# micromouse.net
KiCad netlist of a schematic drawn in EAGLE
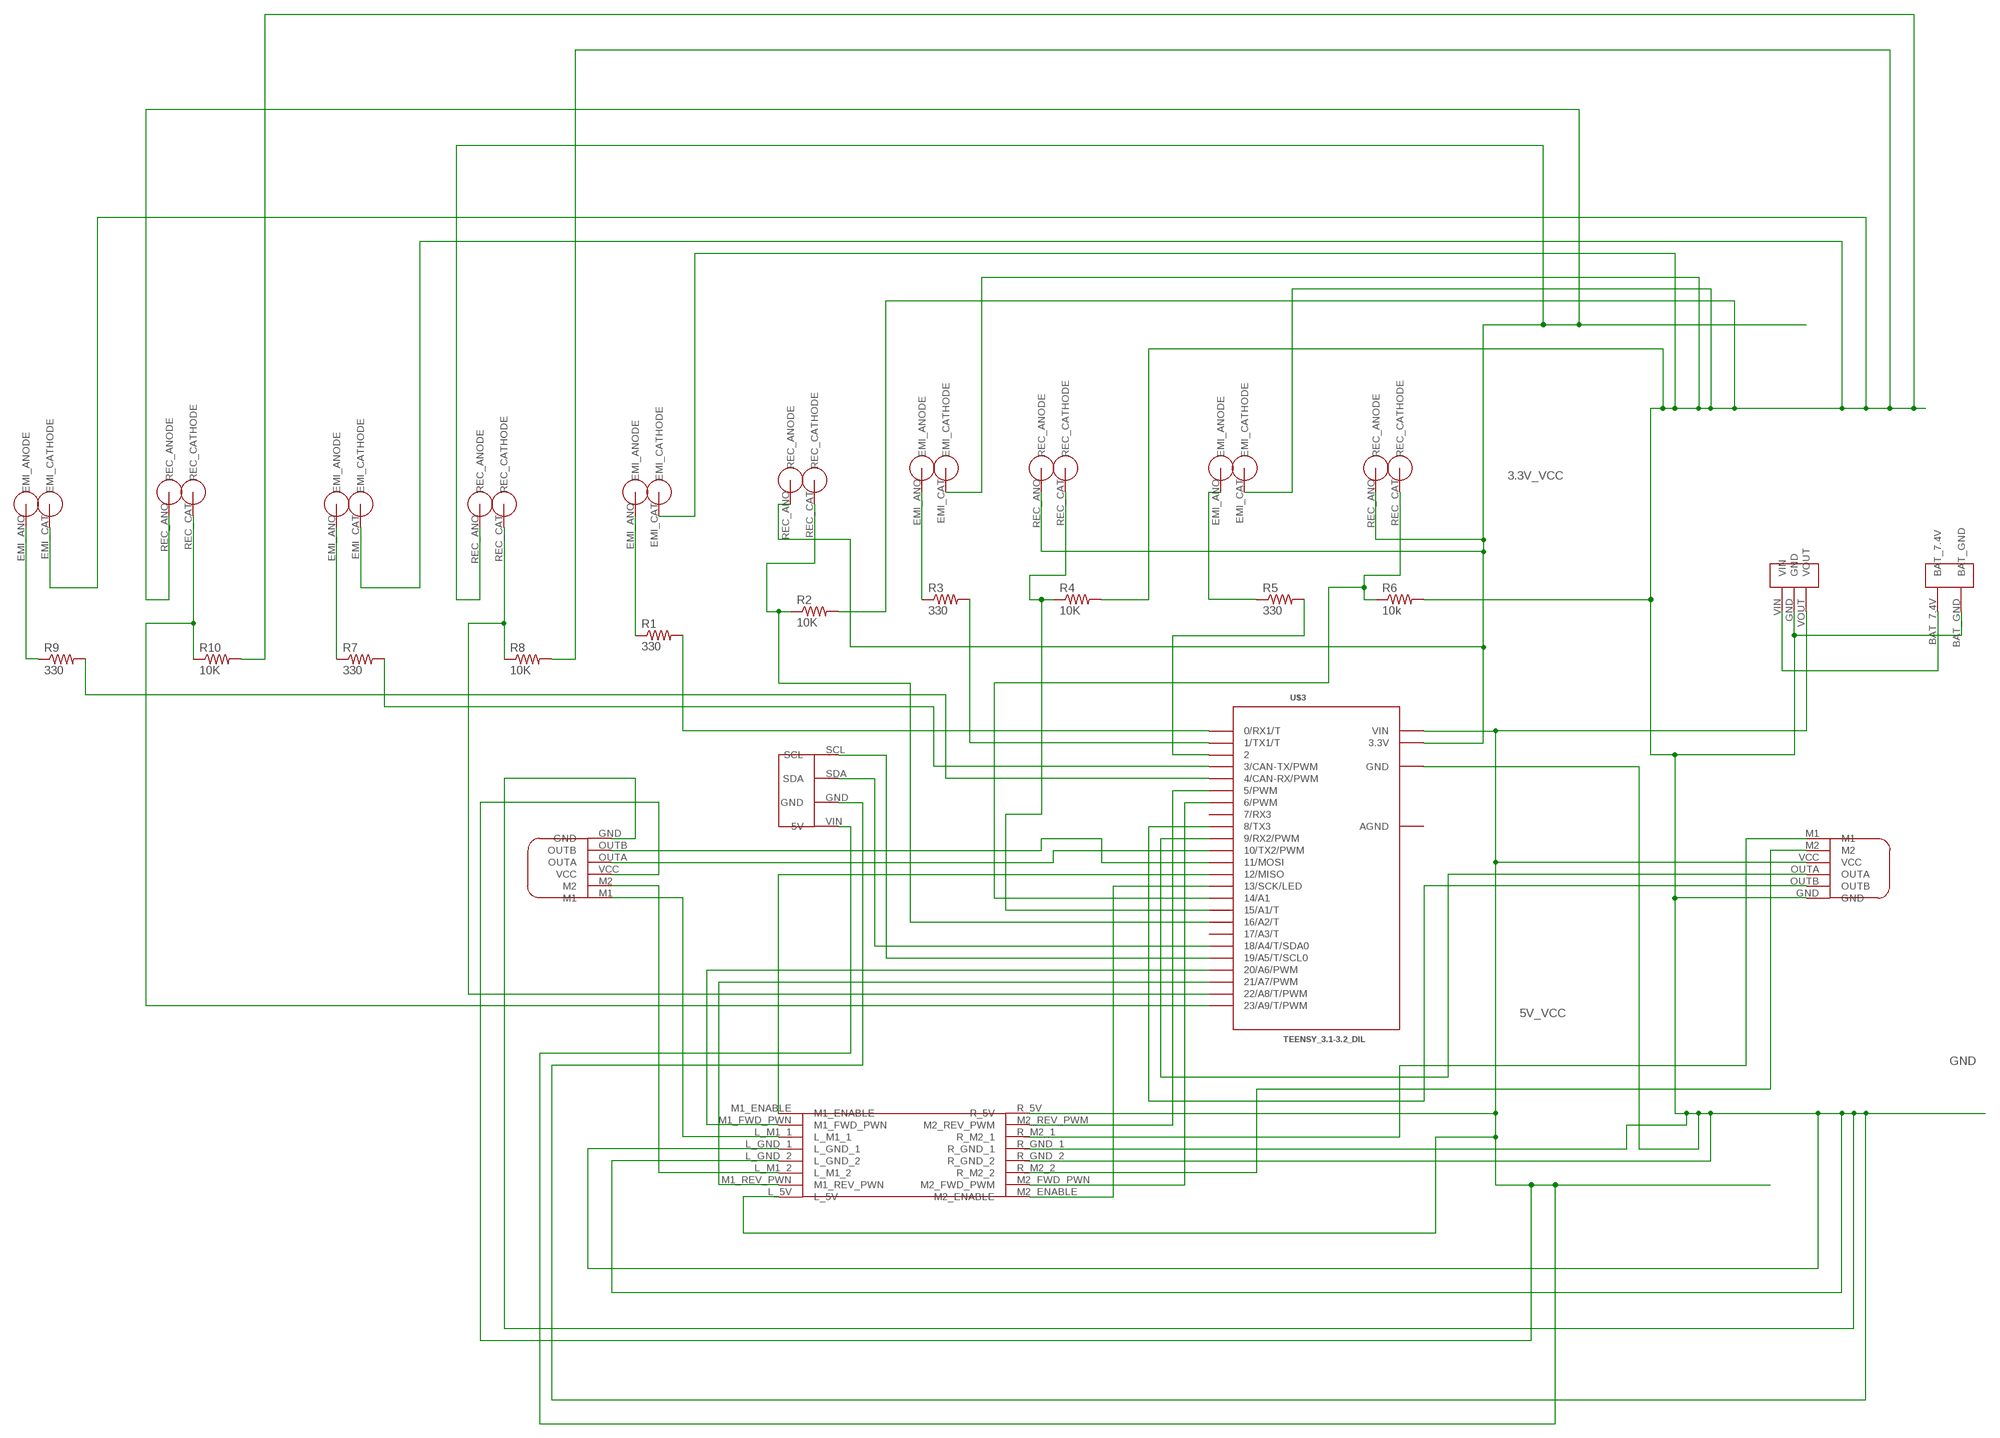
[diagram p0: schematic, sheet 1]

(export (version "E")
  (design (tool "Eeschema 10.0.6"))
  (components
    (comp (ref "R1")
      (value "330")
      (footprint "eagle-import:0207_10")
      (libsource (lib "eagle-import") (part "R-US_0207/10"))
    )
    (comp (ref "R2")
      (value "10K")
      (footprint "eagle-import:0207_10")
      (libsource (lib "eagle-import") (part "R-US_0207/10"))
    )
    (comp (ref "R3")
      (value "330")
      (footprint "eagle-import:0207_10")
      (libsource (lib "eagle-import") (part "R-US_0207/10"))
    )
    (comp (ref "R4")
      (value "10K")
      (footprint "eagle-import:0207_10")
      (libsource (lib "eagle-import") (part "R-US_0207/10"))
    )
    (comp (ref "R5")
      (value "330")
      (footprint "eagle-import:0207_10")
      (libsource (lib "eagle-import") (part "R-US_0207/10"))
    )
    (comp (ref "R6")
      (value "10k")
      (footprint "eagle-import:0207_10")
      (libsource (lib "eagle-import") (part "R-US_0207/10"))
    )
    (comp (ref "R7")
      (value "330")
      (footprint "eagle-import:0207_10")
      (libsource (lib "eagle-import") (part "R-US_0207/10"))
    )
    (comp (ref "R8")
      (value "10K")
      (footprint "eagle-import:0207_10")
      (libsource (lib "eagle-import") (part "R-US_0207/10"))
    )
    (comp (ref "R9")
      (value "330")
      (footprint "eagle-import:0207_10")
      (libsource (lib "eagle-import") (part "R-US_0207/10"))
    )
    (comp (ref "R10")
      (value "10K")
      (footprint "eagle-import:0207_10")
      (libsource (lib "eagle-import") (part "R-US_0207/10"))
    )
    (comp (ref "U$1")
      (value "MOTOR_ENCODER")
      (footprint "eagle-import:MOTOR_ENCODER")
      (libsource (lib "eagle-import") (part "MOTOR_ENCODER"))
    )
    (comp (ref "U$2")
      (value "MOTOR_ENCODER")
      (footprint "eagle-import:MOTOR_ENCODER")
      (libsource (lib "eagle-import") (part "MOTOR_ENCODER"))
    )
    (comp (ref "U$3")
      (value "TEENSY_3.1-3.2_DIL")
      (footprint "eagle-import:TEENSY_3.0-3.2&LC_DIL")
      (libsource (lib "eagle-import") (part "TEENSY_3.1-3.2_DIL"))
    )
    (comp (ref "U$4")
      (value "MOTOR_DRIVER")
      (footprint "eagle-import:MOTOR_DRIVER")
      (libsource (lib "eagle-import") (part "MOTOR_DRIVER"))
    )
    (comp (ref "U$5")
      (value "IR_RECIEVER")
      (footprint "eagle-import:IR_RECIEVER")
      (libsource (lib "eagle-import") (part "IR_RECIEVER"))
    )
    (comp (ref "U$6")
      (value "IR_EMITTER")
      (footprint "eagle-import:IR_EMITTER")
      (libsource (lib "eagle-import") (part "IR_EMITTER"))
    )
    (comp (ref "U$7")
      (value "IR_EMITTER")
      (footprint "eagle-import:IR_EMITTER")
      (libsource (lib "eagle-import") (part "IR_EMITTER"))
    )
    (comp (ref "U$8")
      (value "IR_RECIEVER")
      (footprint "eagle-import:IR_RECIEVER")
      (libsource (lib "eagle-import") (part "IR_RECIEVER"))
    )
    (comp (ref "U$9")
      (value "IR_EMITTER")
      (footprint "eagle-import:IR_EMITTER")
      (libsource (lib "eagle-import") (part "IR_EMITTER"))
    )
    (comp (ref "U$10")
      (value "VOLTAGE_REGULATOR")
      (footprint "eagle-import:VOLTAGE_REGULATOR")
      (libsource (lib "eagle-import") (part "VOLTAGE_REGULATOR"))
    )
    (comp (ref "U$11")
      (value "BATTERY_INPUT")
      (footprint "eagle-import:BATTERY_INPUT")
      (libsource (lib "eagle-import") (part "BATTERY_INPUT"))
    )
    (comp (ref "U$12")
      (value "IR_RECIEVER")
      (footprint "eagle-import:IR_RECIEVER")
      (libsource (lib "eagle-import") (part "IR_RECIEVER"))
    )
    (comp (ref "U$13")
      (value "IMU")
      (footprint "eagle-import:IMU")
      (libsource (lib "eagle-import") (part "IMU"))
    )
    (comp (ref "U$14")
      (value "IR_EMITTER")
      (footprint "eagle-import:IR_EMITTER")
      (libsource (lib "eagle-import") (part "IR_EMITTER"))
    )
    (comp (ref "U$15")
      (value "IR_RECIEVER")
      (footprint "eagle-import:IR_RECIEVER")
      (libsource (lib "eagle-import") (part "IR_RECIEVER"))
    )
    (comp (ref "U$16")
      (value "IR_EMITTER")
      (footprint "eagle-import:IR_EMITTER")
      (libsource (lib "eagle-import") (part "IR_EMITTER"))
    )
    (comp (ref "U$17")
      (value "IR_RECIEVER")
      (footprint "eagle-import:IR_RECIEVER")
      (libsource (lib "eagle-import") (part "IR_RECIEVER"))
    )
  )
  (nets
    (net (code "1") (name "/3.3V_VCC") (class "Default")
      (node (ref "U$12") (pin "REC_ANO") (pinfunction "REC_ANODE_REC_ANO") (pintype "bidirectional"))
      (node (ref "U$15") (pin "REC_ANO") (pinfunction "REC_ANODE_REC_ANO") (pintype "bidirectional"))
      (node (ref "U$17") (pin "REC_ANO") (pinfunction "REC_ANODE_REC_ANO") (pintype "bidirectional"))
      (node (ref "U$3") (pin "3.3V") (pinfunction "3.3V_3.3V") (pintype "power_in"))
      (node (ref "U$5") (pin "REC_ANO") (pinfunction "REC_ANODE_REC_ANO") (pintype "bidirectional"))
      (node (ref "U$8") (pin "REC_ANO") (pinfunction "REC_ANODE_REC_ANO") (pintype "bidirectional"))
    )
    (net (code "2") (name "/5V_VCC") (class "Default")
      (node (ref "U$1") (pin "VCC") (pinfunction "VCC_VCC") (pintype "bidirectional"))
      (node (ref "U$10") (pin "VOUT") (pinfunction "VOUT_VOUT") (pintype "bidirectional"))
      (node (ref "U$13") (pin "VIN") (pinfunction "5V_VIN") (pintype "bidirectional"))
      (node (ref "U$2") (pin "VCC") (pinfunction "VCC_VCC") (pintype "bidirectional"))
      (node (ref "U$3") (pin "VIN") (pinfunction "VIN_VIN") (pintype "power_in"))
      (node (ref "U$4") (pin "L_5V") (pinfunction "L_5V_L_5V") (pintype "bidirectional"))
      (node (ref "U$4") (pin "R_5V") (pinfunction "R_5V_R_5V") (pintype "bidirectional"))
    )
    (net (code "3") (name "/AGND") (class "Default")
      (node (ref "U$3") (pin "AGND") (pinfunction "AGND_AGND") (pintype "power_in"))
    )
    (net (code "4") (name "/GND") (class "Default")
      (node (ref "R10") (pin "2") (pinfunction "2_2") (pintype "passive"))
      (node (ref "R2") (pin "2") (pinfunction "2_2") (pintype "passive"))
      (node (ref "R4") (pin "2") (pinfunction "2_2") (pintype "passive"))
      (node (ref "R6") (pin "2") (pinfunction "2_2") (pintype "passive"))
      (node (ref "R8") (pin "2") (pinfunction "2_2") (pintype "passive"))
      (node (ref "U$1") (pin "GND") (pinfunction "GND_GND") (pintype "bidirectional"))
      (node (ref "U$10") (pin "GND") (pinfunction "GND_GND") (pintype "bidirectional"))
      (node (ref "U$11") (pin "BAT_GND") (pinfunction "BAT_GND_BAT_GND") (pintype "bidirectional"))
      (node (ref "U$13") (pin "GND") (pinfunction "GND_GND") (pintype "bidirectional"))
      (node (ref "U$14") (pin "EMI_CAT") (pinfunction "EMI_CATHODE_EMI_CAT") (pintype "bidirectional"))
      (node (ref "U$16") (pin "EMI_CAT") (pinfunction "EMI_CATHODE_EMI_CAT") (pintype "bidirectional"))
      (node (ref "U$2") (pin "GND") (pinfunction "GND_GND") (pintype "bidirectional"))
      (node (ref "U$3") (pin "GND") (pinfunction "GND_GND") (pintype "power_in"))
      (node (ref "U$4") (pin "L_GND_1") (pinfunction "L_GND_1_L_GND_1") (pintype "bidirectional"))
      (node (ref "U$4") (pin "L_GND_2") (pinfunction "L_GND_2_L_GND_2") (pintype "bidirectional"))
      (node (ref "U$4") (pin "R_GND_1") (pinfunction "R_GND_1_R_GND_1") (pintype "bidirectional"))
      (node (ref "U$4") (pin "R_GND_2") (pinfunction "R_GND_2_R_GND_2") (pintype "bidirectional"))
      (node (ref "U$6") (pin "EMI_CAT") (pinfunction "EMI_CATHODE_EMI_CAT") (pintype "bidirectional"))
      (node (ref "U$7") (pin "EMI_CAT") (pinfunction "EMI_CATHODE_EMI_CAT") (pintype "bidirectional"))
      (node (ref "U$9") (pin "EMI_CAT") (pinfunction "EMI_CATHODE_EMI_CAT") (pintype "bidirectional"))
    )
    (net (code "5") (name "Net-(R5-Pad2)") (class "Default")
      (node (ref "R5") (pin "2") (pinfunction "2_2") (pintype "passive"))
      (node (ref "U$3") (pin "2") (pinfunction "2_2") (pintype "bidirectional"))
    )
    (net (code "6") (name "Net-(U$1-PadM1)") (class "Default")
      (node (ref "U$1") (pin "M1") (pinfunction "M1_M1") (pintype "bidirectional"))
      (node (ref "U$4") (pin "L_M1_1") (pinfunction "L_M1_1_L_M1_1") (pintype "bidirectional"))
    )
    (net (code "7") (name "Net-(U$1-PadM2)") (class "Default")
      (node (ref "U$1") (pin "M2") (pinfunction "M2_M2") (pintype "bidirectional"))
      (node (ref "U$4") (pin "L_M1_2") (pinfunction "L_M1_2_L_M1_2") (pintype "bidirectional"))
    )
    (net (code "8") (name "Net-(U$2-PadM1)") (class "Default")
      (node (ref "U$2") (pin "M1") (pinfunction "M1_M1") (pintype "bidirectional"))
      (node (ref "U$4") (pin "R_M2_1") (pinfunction "R_M2_1_R_M2_1") (pintype "bidirectional"))
    )
    (net (code "9") (name "Net-(U$2-PadM2)") (class "Default")
      (node (ref "U$2") (pin "M2") (pinfunction "M2_M2") (pintype "bidirectional"))
      (node (ref "U$4") (pin "R_M2_2") (pinfunction "R_M2_2_R_M2_2") (pintype "bidirectional"))
    )
    (net (code "10") (name "Net-(U$3-0{slash}RX1{slash}T)") (class "Default")
      (node (ref "R1") (pin "2") (pinfunction "2_2") (pintype "passive"))
      (node (ref "U$3") (pin "0") (pinfunction "0/RX1/T_0") (pintype "bidirectional"))
    )
    (net (code "11") (name "Net-(U$3-1{slash}TX1{slash}T)") (class "Default")
      (node (ref "R3") (pin "2") (pinfunction "2_2") (pintype "passive"))
      (node (ref "U$3") (pin "1") (pinfunction "1/TX1/T_1") (pintype "bidirectional"))
    )
    (net (code "12") (name "Net-(U$3-3{slash}CAN-TX{slash}PWM)") (class "Default")
      (node (ref "R7") (pin "2") (pinfunction "2_2") (pintype "passive"))
      (node (ref "U$3") (pin "3") (pinfunction "3/CAN-TX/PWM_3") (pintype "bidirectional"))
    )
    (net (code "13") (name "Net-(U$3-4{slash}CAN-RX{slash}PWM)") (class "Default")
      (node (ref "R9") (pin "2") (pinfunction "2_2") (pintype "passive"))
      (node (ref "U$3") (pin "4") (pinfunction "4/CAN-RX/PWM_4") (pintype "bidirectional"))
    )
    (net (code "14") (name "Net-(U$3-5{slash}PWM)") (class "Default")
      (node (ref "U$3") (pin "5") (pinfunction "5/PWM_5") (pintype "bidirectional"))
      (node (ref "U$4") (pin "M2_REV_PWM") (pinfunction "M2_REV_PWM_M2_REV_PWM") (pintype "bidirectional"))
    )
    (net (code "15") (name "Net-(U$3-6{slash}PWM)") (class "Default")
      (node (ref "U$3") (pin "6") (pinfunction "6/PWM_6") (pintype "bidirectional"))
      (node (ref "U$4") (pin "M2_FWD_PWN") (pinfunction "M2_FWD_PWM_M2_FWD_PWN") (pintype "bidirectional"))
    )
    (net (code "16") (name "Net-(U$3-8{slash}TX3)") (class "Default")
      (node (ref "U$2") (pin "OUTB") (pinfunction "OUTB_OUTB") (pintype "bidirectional"))
      (node (ref "U$3") (pin "8") (pinfunction "8/TX3_8") (pintype "bidirectional"))
    )
    (net (code "17") (name "Net-(U$3-9{slash}RX2{slash}PWM)") (class "Default")
      (node (ref "U$2") (pin "OUTA") (pinfunction "OUTA_OUTA") (pintype "bidirectional"))
      (node (ref "U$3") (pin "9") (pinfunction "9/RX2/PWM_9") (pintype "bidirectional"))
    )
    (net (code "18") (name "Net-(U$3-10{slash}TX2{slash}PWM)") (class "Default")
      (node (ref "U$1") (pin "OUTA") (pinfunction "OUTA_OUTA") (pintype "bidirectional"))
      (node (ref "U$3") (pin "10") (pinfunction "10/TX2/PWM_10") (pintype "bidirectional"))
    )
    (net (code "19") (name "Net-(U$3-11{slash}MOSI)") (class "Default")
      (node (ref "U$1") (pin "OUTB") (pinfunction "OUTB_OUTB") (pintype "bidirectional"))
      (node (ref "U$3") (pin "11") (pinfunction "11/MOSI_11") (pintype "bidirectional"))
    )
    (net (code "20") (name "Net-(U$3-12{slash}MISO)") (class "Default")
      (node (ref "U$3") (pin "12") (pinfunction "12/MISO_12") (pintype "bidirectional"))
      (node (ref "U$4") (pin "M1_ENABLE") (pinfunction "M1_ENABLE_M1_ENABLE") (pintype "bidirectional"))
    )
    (net (code "21") (name "Net-(U$3-13{slash}SCK{slash}LED)") (class "Default")
      (node (ref "U$3") (pin "13") (pinfunction "13/SCK/LED_13") (pintype "bidirectional"))
      (node (ref "U$4") (pin "M2_ENABLE") (pinfunction "M2_ENABLE_M2_ENABLE") (pintype "bidirectional"))
    )
    (net (code "22") (name "Net-(U$3-14{slash}A1)") (class "Default")
      (node (ref "R6") (pin "1") (pinfunction "1_1") (pintype "passive"))
      (node (ref "U$3") (pin "14/A0") (pinfunction "14/A1_14/A0") (pintype "bidirectional"))
      (node (ref "U$8") (pin "REC_CAT") (pinfunction "REC_CATHODE_REC_CAT") (pintype "bidirectional"))
    )
    (net (code "23") (name "Net-(U$3-16{slash}A2{slash}T)") (class "Default")
      (node (ref "R2") (pin "1") (pinfunction "1_1") (pintype "passive"))
      (node (ref "U$3") (pin "16/A2") (pinfunction "16/A2/T_16/A2") (pintype "bidirectional"))
      (node (ref "U$5") (pin "REC_CAT") (pinfunction "REC_CATHODE_REC_CAT") (pintype "bidirectional"))
    )
    (net (code "24") (name "Net-(U$3-18{slash}A4{slash}T{slash}SDA0)") (class "Default")
      (node (ref "U$13") (pin "SDA") (pinfunction "SDA_SDA") (pintype "bidirectional"))
      (node (ref "U$3") (pin "18/A4") (pinfunction "18/A4/T/SDA0_18/A4") (pintype "bidirectional"))
    )
    (net (code "25") (name "Net-(U$3-19{slash}A5{slash}T{slash}SCL0)") (class "Default")
      (node (ref "U$13") (pin "SCL") (pinfunction "SCL_SCL") (pintype "bidirectional"))
      (node (ref "U$3") (pin "19/A5") (pinfunction "19/A5/T/SCL0_19/A5") (pintype "bidirectional"))
    )
    (net (code "26") (name "Net-(U$3-20{slash}A6{slash}PWM)") (class "Default")
      (node (ref "U$3") (pin "20/A6") (pinfunction "20/A6/PWM_20/A6") (pintype "bidirectional"))
      (node (ref "U$4") (pin "M1_FWD_PWN") (pinfunction "M1_FWD_PWN_M1_FWD_PWN") (pintype "bidirectional"))
    )
    (net (code "27") (name "Net-(U$3-21{slash}A7{slash}PWM)") (class "Default")
      (node (ref "U$3") (pin "21/A7") (pinfunction "21/A7/PWM_21/A7") (pintype "bidirectional"))
      (node (ref "U$4") (pin "M1_REV_PWN") (pinfunction "M1_REV_PWN_M1_REV_PWN") (pintype "bidirectional"))
    )
    (net (code "28") (name "Net-(U$6-EMI_ANODE)") (class "Default")
      (node (ref "R3") (pin "1") (pinfunction "1_1") (pintype "passive"))
      (node (ref "U$6") (pin "EMI_ANO") (pinfunction "EMI_ANODE_EMI_ANO") (pintype "bidirectional"))
    )
    (net (code "29") (name "Net-(U$7-EMI_ANODE)") (class "Default")
      (node (ref "R5") (pin "1") (pinfunction "1_1") (pintype "passive"))
      (node (ref "U$7") (pin "EMI_ANO") (pinfunction "EMI_ANODE_EMI_ANO") (pintype "bidirectional"))
    )
    (net (code "30") (name "Net-(U$9-EMI_ANODE)") (class "Default")
      (node (ref "R1") (pin "1") (pinfunction "1_1") (pintype "passive"))
      (node (ref "U$9") (pin "EMI_ANO") (pinfunction "EMI_ANODE_EMI_ANO") (pintype "bidirectional"))
    )
    (net (code "31") (name "Net-(U$10-PadVIN)") (class "Default")
      (node (ref "U$10") (pin "VIN") (pinfunction "VIN_VIN") (pintype "bidirectional"))
      (node (ref "U$11") (pin "BAT_7.4V") (pinfunction "BAT_7.4V_BAT_7.4V") (pintype "bidirectional"))
    )
    (net (code "32") (name "Net-(U$12-REC_CATHODE)") (class "Default")
      (node (ref "R4") (pin "1") (pinfunction "1_1") (pintype "passive"))
      (node (ref "U$12") (pin "REC_CAT") (pinfunction "REC_CATHODE_REC_CAT") (pintype "bidirectional"))
      (node (ref "U$3") (pin "15/A1") (pinfunction "15/A1/T_15/A1") (pintype "bidirectional"))
    )
    (net (code "33") (name "Net-(U$14-EMI_ANODE)") (class "Default")
      (node (ref "R7") (pin "1") (pinfunction "1_1") (pintype "passive"))
      (node (ref "U$14") (pin "EMI_ANO") (pinfunction "EMI_ANODE_EMI_ANO") (pintype "bidirectional"))
    )
    (net (code "34") (name "Net-(U$15-REC_CATHODE)") (class "Default")
      (node (ref "R8") (pin "1") (pinfunction "1_1") (pintype "passive"))
      (node (ref "U$15") (pin "REC_CAT") (pinfunction "REC_CATHODE_REC_CAT") (pintype "bidirectional"))
      (node (ref "U$3") (pin "22/A8") (pinfunction "22/A8/T/PWM_22/A8") (pintype "bidirectional"))
    )
    (net (code "35") (name "Net-(U$16-EMI_ANODE)") (class "Default")
      (node (ref "R9") (pin "1") (pinfunction "1_1") (pintype "passive"))
      (node (ref "U$16") (pin "EMI_ANO") (pinfunction "EMI_ANODE_EMI_ANO") (pintype "bidirectional"))
    )
    (net (code "36") (name "Net-(U$17-REC_CATHODE)") (class "Default")
      (node (ref "R10") (pin "1") (pinfunction "1_1") (pintype "passive"))
      (node (ref "U$17") (pin "REC_CAT") (pinfunction "REC_CATHODE_REC_CAT") (pintype "bidirectional"))
      (node (ref "U$3") (pin "23/A9") (pinfunction "23/A9/T/PWM_23/A9") (pintype "bidirectional"))
    )
    (net (code "37") (name "unconnected-(U$3-7{slash}RX3-Pad7)") (class "Default")
      (node (ref "U$3") (pin "7") (pinfunction "7/RX3_7") (pintype "bidirectional"))
    )
    (net (code "38") (name "unconnected-(U$3-17{slash}A3{slash}T-Pad17{slash}A3)") (class "Default")
      (node (ref "U$3") (pin "17/A3") (pinfunction "17/A3/T_17/A3") (pintype "bidirectional"))
    )
  )
)
